# Wifi_micro.net
KiCad netlist of a schematic drawn in EAGLE
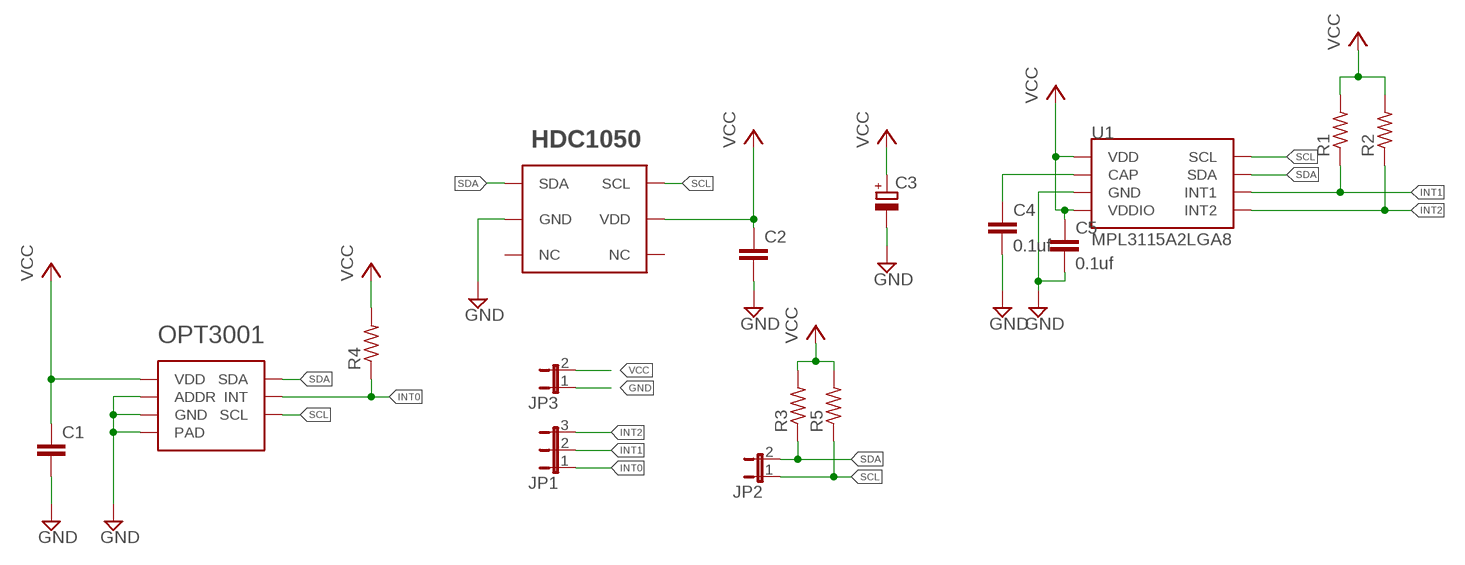
[diagram p0: schematic, sheet 1]

(export (version "E")
  (design (tool "Eeschema 10.0.6"))
  (components
    (comp (ref "C1")
      (value "C-EUC1206")
      (footprint "eagle-import:C1206")
      (libsource (lib "eagle-import") (part "C-EUC1206"))
    )
    (comp (ref "C2")
      (value "C-EUC1206")
      (footprint "eagle-import:C1206")
      (libsource (lib "eagle-import") (part "C-EUC1206"))
    )
    (comp (ref "C3")
      (value "CPOL-EUE2.5-5")
      (footprint "eagle-import:E2,5-5")
      (libsource (lib "eagle-import") (part "CPOL-EUE2.5-5"))
    )
    (comp (ref "C4")
      (value "0.1uf")
      (footprint "eagle-import:C1206")
      (libsource (lib "eagle-import") (part "C-EUC1206"))
    )
    (comp (ref "C5")
      (value "0.1uf")
      (footprint "eagle-import:C1206")
      (libsource (lib "eagle-import") (part "C-EUC1206"))
    )
    (comp (ref "HDC1050")
      (value "HDC1050")
      (footprint "eagle-import:PWSON-6")
      (libsource (lib "eagle-import") (part "HDC1050"))
    )
    (comp (ref "JP1")
      (value "JP2E")
      (footprint "eagle-import:JP2")
      (libsource (lib "eagle-import") (part "JP2E"))
    )
    (comp (ref "JP2")
      (value "JP1E")
      (footprint "eagle-import:JP1")
      (libsource (lib "eagle-import") (part "JP1E"))
    )
    (comp (ref "JP3")
      (value "JP1E")
      (footprint "eagle-import:JP1")
      (libsource (lib "eagle-import") (part "JP1E"))
    )
    (comp (ref "OPT3001")
      (value "OPT3001")
      (footprint "eagle-import:OPT3001")
      (libsource (lib "eagle-import") (part "OPT3001"))
    )
    (comp (ref "R1")
      (value "R-US_0204/5")
      (footprint "eagle-import:0204_5")
      (libsource (lib "eagle-import") (part "resistor_R-US_0204/5"))
    )
    (comp (ref "R2")
      (value "R-US_0204/5")
      (footprint "eagle-import:0204_5")
      (libsource (lib "eagle-import") (part "resistor_R-US_0204/5"))
    )
    (comp (ref "R3")
      (value "R-US_0204/5")
      (footprint "eagle-import:0204_5")
      (libsource (lib "eagle-import") (part "resistor_R-US_0204/5"))
    )
    (comp (ref "R4")
      (value "R-US_0204/5")
      (footprint "eagle-import:0204_5")
      (libsource (lib "eagle-import") (part "R-US_0204/5"))
    )
    (comp (ref "R5")
      (value "R-US_0204/5")
      (footprint "eagle-import:0204_5")
      (libsource (lib "eagle-import") (part "resistor_R-US_0204/5"))
    )
    (comp (ref "U1")
      (value "MPL3115A2LGA8")
      (footprint "eagle-import:LGA8")
      (libsource (lib "eagle-import") (part "MPL3115A2LGA8"))
    )
  )
  (nets
    (net (code "1") (name "GND") (class "Default")
      (node (ref "C1") (pin "2") (pinfunction "2_2") (pintype "passive"))
      (node (ref "C2") (pin "2") (pinfunction "2_2") (pintype "passive"))
      (node (ref "C3") (pin "-") (pinfunction "-_-") (pintype "passive"))
      (node (ref "C4") (pin "2") (pinfunction "2_2") (pintype "passive"))
      (node (ref "C5") (pin "2") (pinfunction "2_2") (pintype "passive"))
      (node (ref "HDC1050") (pin "P$2") (pinfunction "GND_P$2") (pintype "power_in"))
      (node (ref "JP3") (pin "1") (pinfunction "1_1") (pintype "passive"))
      (node (ref "OPT3001") (pin "P$2") (pinfunction "ADDR_P$2") (pintype "input"))
      (node (ref "OPT3001") (pin "P$3") (pinfunction "GND_P$3") (pintype "power_in"))
      (node (ref "OPT3001") (pin "P$7") (pinfunction "PAD_P$7") (pintype "power_in"))
      (node (ref "U1") (pin "3") (pinfunction "GND_3") (pintype "power_in"))
    )
    (net (code "2") (name "INT0") (class "Default")
      (node (ref "JP1") (pin "1") (pinfunction "1_1") (pintype "passive"))
      (node (ref "OPT3001") (pin "P$5") (pinfunction "INT_P$5") (pintype "output"))
      (node (ref "R4") (pin "1") (pinfunction "1_1") (pintype "passive"))
    )
    (net (code "3") (name "INT1") (class "Default")
      (node (ref "JP1") (pin "2") (pinfunction "2_2") (pintype "passive"))
      (node (ref "R1") (pin "1") (pinfunction "1_1") (pintype "passive"))
      (node (ref "U1") (pin "6") (pinfunction "INT1_6") (pintype "output"))
    )
    (net (code "4") (name "INT2") (class "Default")
      (node (ref "JP1") (pin "3") (pinfunction "3_3") (pintype "passive"))
      (node (ref "R2") (pin "1") (pinfunction "1_1") (pintype "passive"))
      (node (ref "U1") (pin "5") (pinfunction "INT2_5") (pintype "output"))
    )
    (net (code "5") (name "Net-(U1-CAP)") (class "Default")
      (node (ref "C4") (pin "1") (pinfunction "1_1") (pintype "passive"))
      (node (ref "U1") (pin "2") (pinfunction "CAP_2") (pintype "power_in"))
    )
    (net (code "6") (name "SCL") (class "Default")
      (node (ref "HDC1050") (pin "P$6") (pinfunction "SCL_P$6") (pintype "bidirectional"))
      (node (ref "JP2") (pin "1") (pinfunction "1_1") (pintype "passive"))
      (node (ref "OPT3001") (pin "P$4") (pinfunction "SCL_P$4") (pintype "input"))
      (node (ref "R5") (pin "1") (pinfunction "1_1") (pintype "passive"))
      (node (ref "U1") (pin "8") (pinfunction "SCL_8") (pintype "bidirectional"))
    )
    (net (code "7") (name "SDA") (class "Default")
      (node (ref "HDC1050") (pin "P$1") (pinfunction "SDA_P$1") (pintype "bidirectional"))
      (node (ref "JP2") (pin "2") (pinfunction "2_2") (pintype "passive"))
      (node (ref "OPT3001") (pin "P$6") (pinfunction "SDA_P$6") (pintype "bidirectional"))
      (node (ref "R3") (pin "1") (pinfunction "1_1") (pintype "passive"))
      (node (ref "U1") (pin "7") (pinfunction "SDA_7") (pintype "bidirectional"))
    )
    (net (code "8") (name "VCC") (class "Default")
      (node (ref "C1") (pin "1") (pinfunction "1_1") (pintype "passive"))
      (node (ref "C2") (pin "1") (pinfunction "1_1") (pintype "passive"))
      (node (ref "C3") (pin "+") (pinfunction "+_+") (pintype "passive"))
      (node (ref "C5") (pin "1") (pinfunction "1_1") (pintype "passive"))
      (node (ref "HDC1050") (pin "P$5") (pinfunction "VDD_P$5") (pintype "power_in"))
      (node (ref "JP3") (pin "2") (pinfunction "2_2") (pintype "passive"))
      (node (ref "OPT3001") (pin "P$1") (pinfunction "VDD_P$1") (pintype "power_in"))
      (node (ref "R1") (pin "2") (pinfunction "2_2") (pintype "passive"))
      (node (ref "R2") (pin "2") (pinfunction "2_2") (pintype "passive"))
      (node (ref "R3") (pin "2") (pinfunction "2_2") (pintype "passive"))
      (node (ref "R4") (pin "2") (pinfunction "2_2") (pintype "passive"))
      (node (ref "R5") (pin "2") (pinfunction "2_2") (pintype "passive"))
      (node (ref "U1") (pin "1") (pinfunction "VDD_1") (pintype "power_in"))
      (node (ref "U1") (pin "4") (pinfunction "VDDIO_4") (pintype "power_in"))
    )
    (net (code "9") (name "unconnected-(HDC1050-NC-PadP$3)") (class "Default")
      (node (ref "HDC1050") (pin "P$3") (pinfunction "NC_P$3") (pintype "no_connect"))
    )
    (net (code "10") (name "unconnected-(HDC1050-NC-PadP$4)") (class "Default")
      (node (ref "HDC1050") (pin "P$4") (pinfunction "NC_P$4") (pintype "no_connect"))
    )
  )
)
